# Sheet_1.net
KiCad netlist of a schematic drawn in Altium Designer
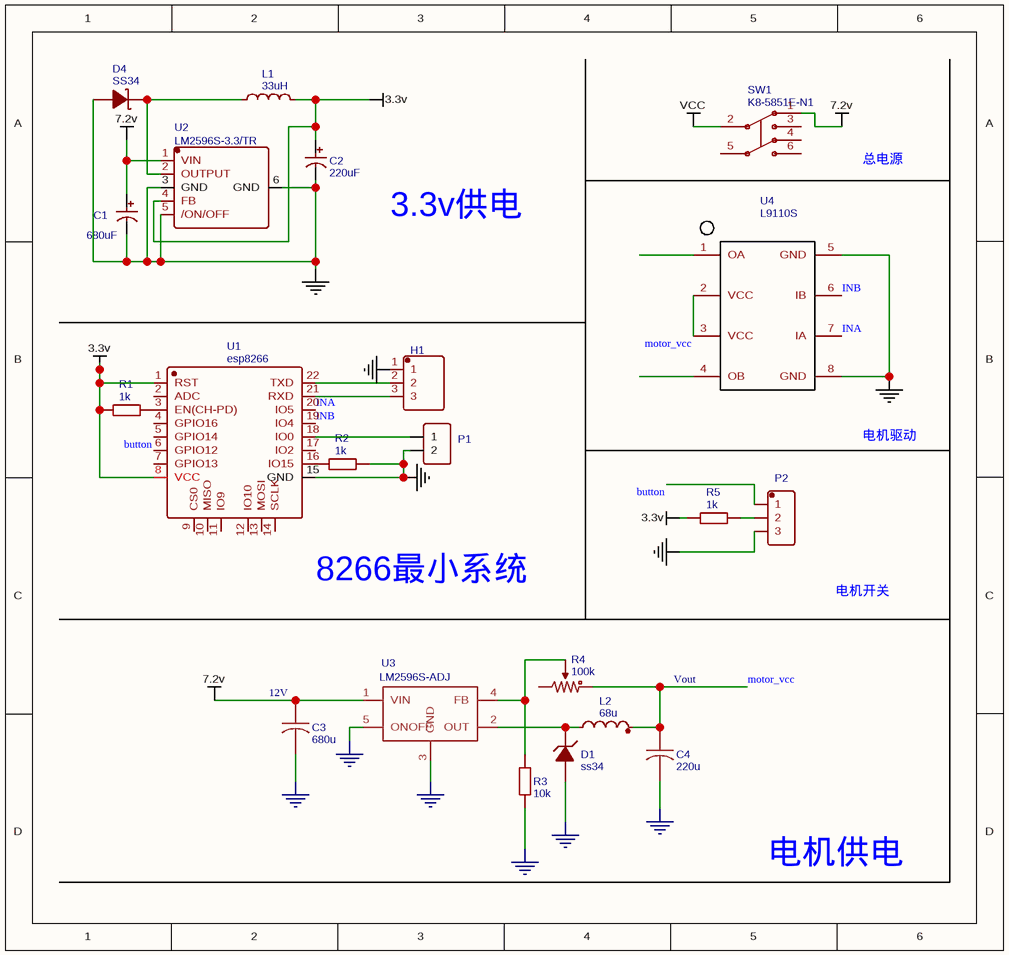
[diagram p0: Sheet_1.schdoc]

(export (version "E")
  (design (tool "Eeschema 10.0.6"))
  (components
    (comp (ref "C1")
      (value "680uF")
      (fields
        (field (name "BOM_MANUFACTURER PART") "680uF 16V绿金 8*12")
        (field (name "BOM_SUPPLIER PART") "C43826")
      )
      (libsource (lib "altium-import") (part "root_3_680uF_"))
    )
    (comp (ref "C2")
      (value "220uF")
      (fields (field (name "BOM_MANUFACTURER PART") "220uf/63V") (field (name "BOM_SUPPLIER PART") "C47290"))
      (libsource (lib "altium-import") (part "root_3_220uF_"))
    )
    (comp (ref "C3")
      (value "680u")
      (fields (field (name "BOM_MANUFACTURER PART") "?"))
      (libsource (lib "altium-import") (part "root_0_680u_"))
    )
    (comp (ref "C4")
      (value "220u")
      (fields (field (name "BOM_MANUFACTURER PART") "?"))
      (libsource (lib "altium-import") (part "root_0_220u_"))
    )
    (comp (ref "D1")
      (value "ss34")
      (fields (field (name "BOM_MANUFACTURER PART") "?"))
      (libsource (lib "altium-import") (part "root_1_ss34_"))
    )
    (comp (ref "D4")
      (value "SS34")
      (fields (field (name "BOM_SUPPLIER PART") "C142458") (field (name "CONTRIBUTOR") "LCSC"))
      (libsource (lib "altium-import") (part "root_0_SS34_"))
    )
    (comp (ref "H1")
      (value "串口")
      (fields
        (field (name "BOM_SUPPLIER PART") "C168677")
        (field (name "BOM_MANUFACTURER PART") "68000-103HLF")
        (field (name "CONTRIBUTOR") "LCSC")
      )
      (libsource (lib "altium-import") (part "root_0_串口_"))
    )
    (comp (ref "L1")
      (value "33uH")
      (fields
        (field (name "BOM_SUPPLIER PART") "C340215")
        (field (name "BOM_MANUFACTURER PART") "ASWPA4035S330MT")
        (field (name "CONTRIBUTOR") "LCSC")
      )
      (libsource (lib "altium-import") (part "root_0_33uH_"))
    )
    (comp (ref "L2")
      (value "68u")
      (fields (field (name "BOM_MANUFACTURER PART") "?"))
      (libsource (lib "altium-import") (part "root_0_68u_"))
    )
    (comp (ref "P1")
      (value "Header-Female-2.54_1x2")
      (fields
        (field (name "BOM_MANUFACTURER PART") "2.54-1*2PFemale")
        (field (name "BOM_SUPPLIER PART") "C49661")
      )
      (libsource (lib "altium-import") (part "root_0_Header-Female-2.54_1x2_"))
    )
    (comp (ref "P2")
      (value "WJ2EDGVC-5.08-3P")
      (fields (field (name "BOM_SUPPLIER PART") "C8430"))
      (libsource (lib "altium-import") (part "root_0_WJ2EDGVC-5.08-3P_"))
    )
    (comp (ref "R1")
      (value "1k")
      (fields (field (name "BOM_MANUFACTURER PART") "?"))
      (libsource (lib "altium-import") (part "root_0_1k_"))
    )
    (comp (ref "R2")
      (value "1k")
      (fields (field (name "BOM_MANUFACTURER PART") "?"))
      (libsource (lib "altium-import") (part "root_0_1k_"))
    )
    (comp (ref "R3")
      (value "10k")
      (fields (field (name "BOM_MANUFACTURER PART") "?"))
      (libsource (lib "altium-import") (part "root_1_10k_"))
    )
    (comp (ref "R4")
      (value "100k")
      (fields (field (name "BOM_MANUFACTURER PART") "?"))
      (libsource (lib "altium-import") (part "root_0_100k_"))
    )
    (comp (ref "R5")
      (value "1k")
      (fields (field (name "BOM_MANUFACTURER PART") "?"))
      (libsource (lib "altium-import") (part "root_0_1k_"))
    )
    (comp (ref "SW1")
      (value "K8-5851E-N1")
      (fields (field (name "BOM_SUPPLIER PART") "C134191") (field (name "CONTRIBUTOR") "LCSC"))
      (libsource (lib "altium-import") (part "root_0_K8-5851E-N1_"))
    )
    (comp (ref "U1")
      (value "esp8266")
      (fields
        (field (name "BOM_MANUFACTURER PART") "ESP-12F(ESP8266MOD)")
        (field (name "BOM_SUPPLIER PART") "C82891")
      )
      (libsource (lib "altium-import") (part "root_0_esp8266_"))
    )
    (comp (ref "U2")
      (value "LM2596S-3.3/TR")
      (fields (field (name "BOM_SUPPLIER PART") "C194350") (field (name "CONTRIBUTOR") "LCSC"))
      (libsource (lib "altium-import") (part "root_0_LM2596S-3.3/TR_"))
    )
    (comp (ref "U3")
      (value "LM2596S-ADJ")
      (fields (field (name "BOM_MANUFACTURER PART") "?") (field (name "CONTRIBUTOR") "KiCad"))
      (libsource (lib "altium-import") (part "root_0_LM2596S-ADJ_"))
    )
    (comp (ref "U4")
      (value "L9110S")
      (fields (field (name "BOM_MANUFACTURER PART") "?") (field (name "CONTRIBUTOR") "h1997l1997"))
      (libsource (lib "altium-import") (part "root_0_L9110S_"))
    )
  )
  (nets
    (net (code "1") (name "/INA") (class "Default")
      (node (ref "U1") (pin "20") (pinfunction "IO5_20") (pintype "passive"))
      (node (ref "U4") (pin "7") (pinfunction "IA_7") (pintype "passive"))
    )
    (net (code "2") (name "/INB") (class "Default")
      (node (ref "U1") (pin "19") (pinfunction "IO4_19") (pintype "passive"))
      (node (ref "U4") (pin "6") (pinfunction "IB_6") (pintype "passive"))
    )
    (net (code "3") (name "/Vout") (class "Default")
      (node (ref "C4") (pin "1") (pinfunction "1_1") (pintype "passive"))
      (node (ref "L2") (pin "2") (pinfunction "2_2") (pintype "passive"))
      (node (ref "R4") (pin "3") (pinfunction "2_3") (pintype "passive"))
      (node (ref "U4") (pin "2") (pinfunction "VCC_2") (pintype "passive"))
      (node (ref "U4") (pin "3") (pinfunction "VCC_3") (pintype "passive"))
    )
    (net (code "4") (name "/button") (class "Default")
      (node (ref "P2") (pin "1") (pinfunction "1_1") (pintype "passive"))
      (node (ref "U1") (pin "5") (pinfunction "GPIO14_5") (pintype "passive"))
    )
    (net (code "5") (name "3.3v") (class "Default")
      (node (ref "C2") (pin "1") (pinfunction "1_1") (pintype "passive"))
      (node (ref "L1") (pin "2") (pinfunction "2_2") (pintype "passive"))
      (node (ref "R1") (pin "1") (pinfunction "1_1") (pintype "passive"))
      (node (ref "R5") (pin "1") (pinfunction "1_1") (pintype "passive"))
      (node (ref "U1") (pin "1") (pinfunction "RST_1") (pintype "passive"))
      (node (ref "U1") (pin "8") (pinfunction "VCC_8") (pintype "passive"))
      (node (ref "U2") (pin "4") (pinfunction "FB_4") (pintype "passive"))
    )
    (net (code "6") (name "7.2v") (class "Default")
      (node (ref "C1") (pin "1") (pinfunction "1_1") (pintype "passive"))
      (node (ref "C3") (pin "1") (pinfunction "1_1") (pintype "passive"))
      (node (ref "SW1") (pin "1") (pinfunction "1_1") (pintype "passive"))
      (node (ref "U2") (pin "1") (pinfunction "VIN_1") (pintype "passive"))
      (node (ref "U3") (pin "1") (pinfunction "VIN_1") (pintype "passive"))
    )
    (net (code "7") (name "GND") (class "Default")
      (node (ref "C1") (pin "2") (pinfunction "2_2") (pintype "passive"))
      (node (ref "C2") (pin "2") (pinfunction "2_2") (pintype "passive"))
      (node (ref "C3") (pin "2") (pinfunction "2_2") (pintype "passive"))
      (node (ref "C4") (pin "2") (pinfunction "2_2") (pintype "passive"))
      (node (ref "D1") (pin "1") (pinfunction "A_1") (pintype "passive"))
      (node (ref "D4") (pin "1") (pinfunction "A_1") (pintype "passive"))
      (node (ref "H1") (pin "1") (pinfunction "1_1") (pintype "passive"))
      (node (ref "P1") (pin "2") (pinfunction "2_2") (pintype "passive"))
      (node (ref "P2") (pin "3") (pinfunction "3_3") (pintype "passive"))
      (node (ref "R2") (pin "2") (pinfunction "2_2") (pintype "passive"))
      (node (ref "R3") (pin "1") (pinfunction "1_1") (pintype "passive"))
      (node (ref "U1") (pin "15") (pinfunction "GND_15") (pintype "passive"))
      (node (ref "U2") (pin "3") (pinfunction "GND_3") (pintype "passive"))
      (node (ref "U2") (pin "5") (pinfunction "/ON/OFF_5") (pintype "passive"))
      (node (ref "U2") (pin "6") (pinfunction "GND_6") (pintype "passive"))
      (node (ref "U3") (pin "3") (pinfunction "GND_3") (pintype "passive"))
      (node (ref "U3") (pin "5") (pinfunction "ONOFF_5") (pintype "passive"))
      (node (ref "U4") (pin "5") (pinfunction "GND_5") (pintype "passive"))
      (node (ref "U4") (pin "8") (pinfunction "GND_8") (pintype "passive"))
    )
    (net (code "8") (name "Net-(D1-K)") (class "Default")
      (node (ref "D1") (pin "2") (pinfunction "K_2") (pintype "passive"))
      (node (ref "L2") (pin "1") (pinfunction "1_1") (pintype "passive"))
      (node (ref "U3") (pin "2") (pinfunction "OUT_2") (pintype "passive"))
    )
    (net (code "9") (name "Net-(D4-K)") (class "Default")
      (node (ref "D4") (pin "2") (pinfunction "K_2") (pintype "passive"))
      (node (ref "L1") (pin "1") (pinfunction "1_1") (pintype "passive"))
      (node (ref "U2") (pin "2") (pinfunction "OUTPUT_2") (pintype "passive"))
    )
    (net (code "10") (name "Net-(P2-Pad2)") (class "Default")
      (node (ref "P2") (pin "2") (pinfunction "2_2") (pintype "passive"))
      (node (ref "R5") (pin "2") (pinfunction "2_2") (pintype "passive"))
    )
    (net (code "11") (name "Net-(R4-3)") (class "Default")
      (node (ref "R3") (pin "2") (pinfunction "2_2") (pintype "passive"))
      (node (ref "R4") (pin "2") (pinfunction "3_2") (pintype "passive"))
      (node (ref "U3") (pin "4") (pinfunction "FB_4") (pintype "passive"))
    )
    (net (code "12") (name "Net-(U1-EN(CH-PD))") (class "Default")
      (node (ref "R1") (pin "2") (pinfunction "2_2") (pintype "passive"))
      (node (ref "U1") (pin "3") (pinfunction "EN(CH-PD)_3") (pintype "passive"))
    )
    (net (code "13") (name "Net-(U1-IO0)") (class "Default")
      (node (ref "P1") (pin "1") (pinfunction "1_1") (pintype "passive"))
      (node (ref "U1") (pin "18") (pinfunction "IO0_18") (pintype "passive"))
    )
    (net (code "14") (name "Net-(U1-IO15)") (class "Default")
      (node (ref "R2") (pin "1") (pinfunction "1_1") (pintype "passive"))
      (node (ref "U1") (pin "16") (pinfunction "IO15_16") (pintype "passive"))
    )
    (net (code "15") (name "Net-(U1-RXD)") (class "Default")
      (node (ref "H1") (pin "3") (pinfunction "3_3") (pintype "passive"))
      (node (ref "U1") (pin "21") (pinfunction "RXD_21") (pintype "passive"))
    )
    (net (code "16") (name "Net-(U1-TXD)") (class "Default")
      (node (ref "H1") (pin "2") (pinfunction "2_2") (pintype "passive"))
      (node (ref "U1") (pin "22") (pinfunction "TXD_22") (pintype "passive"))
    )
    (net (code "17") (name "VCC") (class "Default")
      (node (ref "SW1") (pin "2") (pinfunction "2_2") (pintype "passive"))
    )
    (net (code "18") (name "unconnected-(R4-Pad1)") (class "Default")
      (node (ref "R4") (pin "1") (pinfunction "1_1") (pintype "passive"))
    )
    (net (code "19") (name "unconnected-(SW1-Pad3)") (class "Default")
      (node (ref "SW1") (pin "3") (pinfunction "3_3") (pintype "passive"))
    )
    (net (code "20") (name "unconnected-(SW1-Pad4)") (class "Default")
      (node (ref "SW1") (pin "4") (pinfunction "4_4") (pintype "passive"))
    )
    (net (code "21") (name "unconnected-(SW1-Pad5)") (class "Default")
      (node (ref "SW1") (pin "5") (pinfunction "5_5") (pintype "passive"))
    )
    (net (code "22") (name "unconnected-(SW1-Pad6)") (class "Default")
      (node (ref "SW1") (pin "6") (pinfunction "6_6") (pintype "passive"))
    )
    (net (code "23") (name "unconnected-(U1-ADC-Pad2)") (class "Default")
      (node (ref "U1") (pin "2") (pinfunction "ADC_2") (pintype "passive"))
    )
    (net (code "24") (name "unconnected-(U1-CS0-Pad9)") (class "Default")
      (node (ref "U1") (pin "9") (pinfunction "CS0_9") (pintype "passive"))
    )
    (net (code "25") (name "unconnected-(U1-GPIO12-Pad6)") (class "Default")
      (node (ref "U1") (pin "6") (pinfunction "GPIO12_6") (pintype "passive"))
    )
    (net (code "26") (name "unconnected-(U1-GPIO13-Pad7)") (class "Default")
      (node (ref "U1") (pin "7") (pinfunction "GPIO13_7") (pintype "passive"))
    )
    (net (code "27") (name "unconnected-(U1-GPIO16-Pad4)") (class "Default")
      (node (ref "U1") (pin "4") (pinfunction "GPIO16_4") (pintype "passive"))
    )
    (net (code "28") (name "unconnected-(U1-IO2-Pad17)") (class "Default")
      (node (ref "U1") (pin "17") (pinfunction "IO2_17") (pintype "passive"))
    )
    (net (code "29") (name "unconnected-(U1-IO9-Pad11)") (class "Default")
      (node (ref "U1") (pin "11") (pinfunction "IO9_11") (pintype "passive"))
    )
    (net (code "30") (name "unconnected-(U1-IO10-Pad12)") (class "Default")
      (node (ref "U1") (pin "12") (pinfunction "IO10_12") (pintype "passive"))
    )
    (net (code "31") (name "unconnected-(U1-MISO-Pad10)") (class "Default")
      (node (ref "U1") (pin "10") (pinfunction "MISO_10") (pintype "passive"))
    )
    (net (code "32") (name "unconnected-(U1-MOSI-Pad13)") (class "Default")
      (node (ref "U1") (pin "13") (pinfunction "MOSI_13") (pintype "passive"))
    )
    (net (code "33") (name "unconnected-(U1-SCLK-Pad14)") (class "Default")
      (node (ref "U1") (pin "14") (pinfunction "SCLK_14") (pintype "passive"))
    )
    (net (code "34") (name "unconnected-(U4-OA-Pad1)") (class "Default")
      (node (ref "U4") (pin "1") (pinfunction "OA_1") (pintype "passive"))
    )
    (net (code "35") (name "unconnected-(U4-OB-Pad4)") (class "Default")
      (node (ref "U4") (pin "4") (pinfunction "OB_4") (pintype "passive"))
    )
  )
)
